# SPDIF.net
KiCad netlist of a schematic drawn in Altium Designer
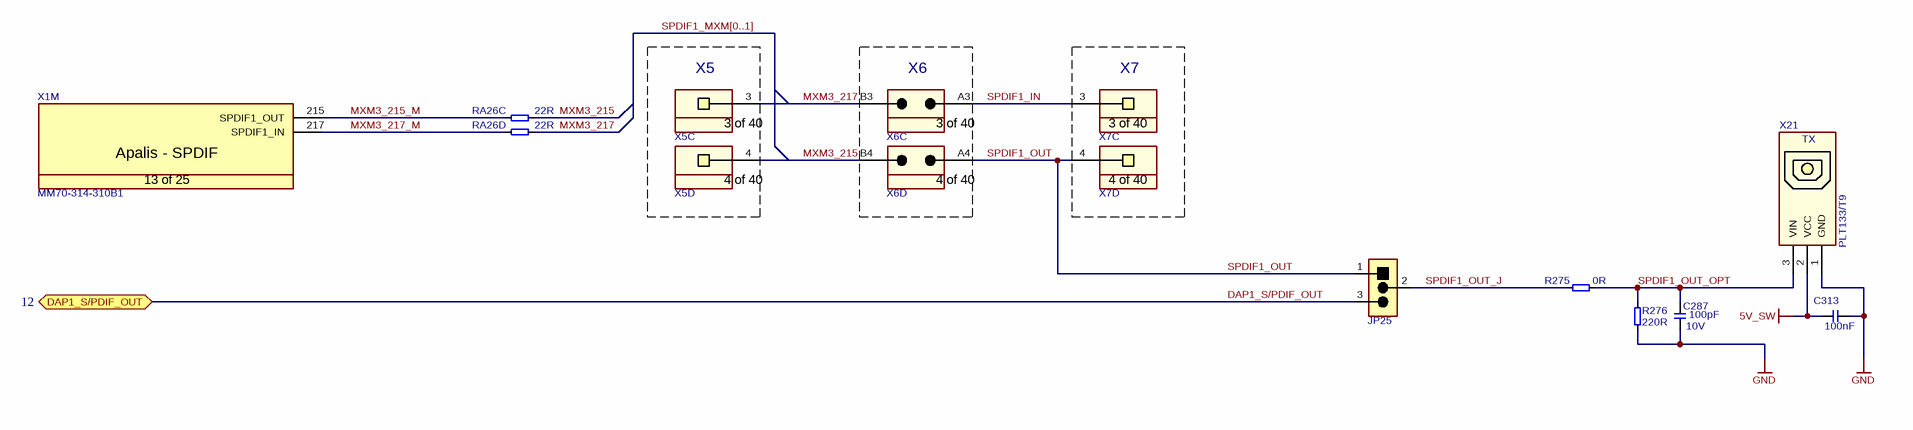
[diagram p0: SPDIF.SchDoc]

(export (version "E")
  (design (tool "Eeschema 10.0.6"))
  (components
    (comp (ref "C287")
      (value "100pF")
      (footprint "T_CAPC0603X33N")
      (description "Capacitor Ceramic X7R 100pF 10V 20% 0603")
      (fields (field (name "TOLERANCE") "20%") (field (name "RATING") "10V"))
      (libsource (lib "Apalis Evaluation Board") (part "C-X7R-100pF-10V-20%-0603"))
    )
    (comp (ref "C313")
      (value "100nF")
      (footprint "T_CAPC0603X33N")
      (description "Capacitor Ceramic X7R 100nF 16V 10% 0603")
      (fields (field (name "TOLERANCE") "10%"))
      (libsource (lib "Apalis Evaluation Board") (part "C-X7R-100nF-16V-10%-0603"))
    )
    (comp (ref "JP25")
      (value "826936-3")
      (footprint "T_TYCO_826936-3")
      (description "Jumper, 3-Pin")
      (libsource (lib "Apalis Evaluation Board") (part "CON-Tyco-826936-3-1X3-2.54mm-JP_1"))
    )
    (comp (ref "R275")
      (value "0R")
      (footprint "T_RESC0603X30N")
      (description "Resistor 0 ohm 63mW 1% 0603")
      (fields (field (name "TOLERANCE") "1%"))
      (libsource (lib "Apalis Evaluation Board") (part "R-0R-63mW-1%-0603"))
    )
    (comp (ref "R276")
      (value "220R")
      (footprint "T_RESC0603X30N")
      (description "Resistor 220 ohm 63mW 5% 0603")
      (fields (field (name "TOLERANCE") "5%"))
      (libsource (lib "Apalis Evaluation Board") (part "R-220R-63mW-5%-0603"))
    )
    (comp (ref "RA26")
      (value "22R")
      (footprint "T_Resistor_Array_X4")
      (description "Resistor Array 22 R 63mW 5% 1206")
      (fields (field (name "TOLERANCE") "5%"))
      (libsource (lib "Apalis Evaluation Board") (part "RA-22R-63mW-5%-1206-div"))
    )
    (comp (ref "X1")
      (value "CON-JAE-MM70-314-310B1-314-0.5mm")
      (footprint "T_JAE_MM70-314-310B1")
      (description "MXM3 Connector")
      (fields (field (name "MANUFACTURER PART NO.") "MM70-314-310B1"))
      (libsource (lib "Apalis Evaluation Board") (part "CON-JAE-MM70-314-310B1-314-0.5mm"))
    )
    (comp (ref "X5")
      (value "SSW-110-01-G-S")
      (footprint "T_Samtec_SSW-110-01-G-S")
      (description "Receptacle Female Socket 1x40 pin 2.54mm pitch")
      (libsource (lib "Apalis Evaluation Board") (part "CON-Samtec-SSW-110-01-G-S"))
    )
    (comp (ref "X6")
      (value "TSW-110-07-G-D")
      (footprint "T_Samtec_TSW-110-07-G-D")
      (description "Header 2x40 pin 2.54mm pitch")
      (libsource (lib "Apalis Evaluation Board") (part "CON-Samtec-TSW-110-07-G-D"))
    )
    (comp (ref "X7")
      (value "SSW-110-01-G-S")
      (footprint "T_Samtec_SSW-110-01-G-S")
      (description "Receptacle Female Socket 1x40 pin 2.54mm pitch")
      (libsource (lib "") (part "CON-Samtec-SSW-110-01-G-S_1"))
    )
    (comp (ref "X21")
      (value "PLT133/T9")
      (footprint "T_EVERLIGHT_PLT133/T9")
      (description "Photolink- Fiber Optic Transmitter")
      (fields (field (name "MANUFACTURER PART NO.") "PLT133/T9"))
      (libsource (lib "Apalis Evaluation Board") (part "IF-Everlight-PLT133/T9"))
    )
  )
  (nets
    (net (code "3") (name "/DAP1_S{slash}PDIF_OUT") (class "Default")
      (node (ref "JP25") (pin "3") (pinfunction "3_3") (pintype "passive"))
    )
    (net (code "4") (name "/MXM3_215") (class "Default")
      (node (ref "RA26") (pin "7") (pinfunction "7_7") (pintype "passive"))
      (node (ref "X5") (pin "4") (pinfunction "4_4") (pintype "passive"))
      (node (ref "X6") (pin "B4") (pinfunction "B4_B4") (pintype "passive"))
    )
    (net (code "5") (name "/MXM3_215_M") (class "Default")
      (node (ref "RA26") (pin "3") (pinfunction "3_3") (pintype "passive"))
      (node (ref "X1") (pin "215") (pinfunction "SPDIF1_OUT_215") (pintype "passive"))
    )
    (net (code "6") (name "/MXM3_217") (class "Default")
      (node (ref "RA26") (pin "8") (pinfunction "8_8") (pintype "passive"))
      (node (ref "X5") (pin "3") (pinfunction "3_3") (pintype "passive"))
      (node (ref "X6") (pin "B3") (pinfunction "B3_B3") (pintype "passive"))
    )
    (net (code "7") (name "/MXM3_217_M") (class "Default")
      (node (ref "RA26") (pin "4") (pinfunction "4_4") (pintype "passive"))
      (node (ref "X1") (pin "217") (pinfunction "SPDIF1_IN_217") (pintype "passive"))
    )
    (net (code "8") (name "/SPDIF1_IN") (class "Default")
      (node (ref "X6") (pin "A3") (pinfunction "A3_A3") (pintype "passive"))
      (node (ref "X7") (pin "3") (pinfunction "3_3") (pintype "passive"))
    )
    (net (code "10") (name "/SPDIF1_OUT") (class "Default")
      (node (ref "JP25") (pin "1") (pinfunction "1_1") (pintype "passive"))
      (node (ref "X6") (pin "A4") (pinfunction "A4_A4") (pintype "passive"))
      (node (ref "X7") (pin "4") (pinfunction "4_4") (pintype "passive"))
    )
    (net (code "11") (name "/SPDIF1_OUT_J") (class "Default")
      (node (ref "JP25") (pin "2") (pinfunction "2_2") (pintype "passive"))
      (node (ref "R275") (pin "1") (pinfunction "1_1") (pintype "passive"))
    )
    (net (code "12") (name "/SPDIF1_OUT_OPT") (class "Default")
      (node (ref "C287") (pin "2") (pinfunction "2_2") (pintype "passive"))
      (node (ref "R275") (pin "2") (pinfunction "2_2") (pintype "passive"))
      (node (ref "R276") (pin "2") (pinfunction "2_2") (pintype "passive"))
      (node (ref "X21") (pin "3") (pinfunction "VIN_3") (pintype "passive"))
    )
    (net (code "13") (name "5V_SW") (class "Default")
      (node (ref "C313") (pin "1") (pinfunction "1_1") (pintype "passive"))
      (node (ref "X21") (pin "2") (pinfunction "VCC_2") (pintype "passive"))
    )
    (net (code "14") (name "GND") (class "Default")
      (node (ref "C287") (pin "1") (pinfunction "1_1") (pintype "passive"))
      (node (ref "C313") (pin "2") (pinfunction "2_2") (pintype "passive"))
      (node (ref "R276") (pin "1") (pinfunction "1_1") (pintype "passive"))
      (node (ref "X21") (pin "1") (pinfunction "GND_1") (pintype "passive"))
    )
  )
)
